# Power.net
KiCad netlist of a schematic drawn in Altium Designer
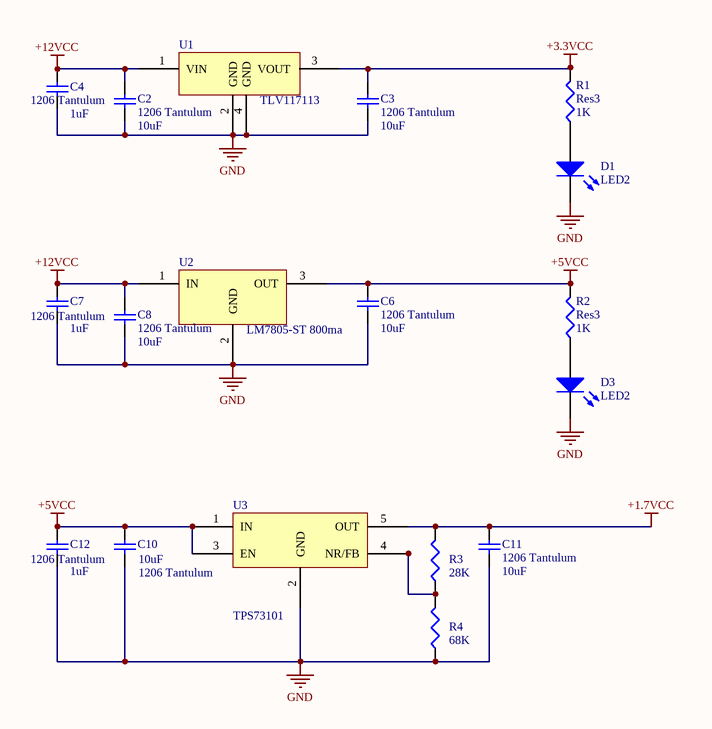
[diagram p0: Power.SchDoc]

(export (version "E")
  (design (tool "Eeschema 10.0.6"))
  (components
    (comp (ref "C2")
      (value "1206 Tantulum")
      (footprint "C1206")
      (description "Capacitor (Semiconductor SIM Model)")
      (fields (field (name "ALTIUM_VALUE") "10uF") (field (name "PUBLISHER") "Altium Limited"))
      (libsource (lib "Miscellaneous Devices") (part "Cap Semi"))
    )
    (comp (ref "C3")
      (value "1206 Tantulum")
      (footprint "C1206")
      (description "Capacitor (Semiconductor SIM Model)")
      (fields (field (name "ALTIUM_VALUE") "10uF") (field (name "PUBLISHER") "Altium Limited"))
      (libsource (lib "Miscellaneous Devices") (part "Cap Semi"))
    )
    (comp (ref "C4")
      (value "1206 Tantulum")
      (footprint "C1206")
      (description "Capacitor (Semiconductor SIM Model)")
      (fields (field (name "ALTIUM_VALUE") "1uF") (field (name "PUBLISHER") "Altium Limited"))
      (libsource (lib "Miscellaneous Devices") (part "Cap Semi"))
    )
    (comp (ref "C6")
      (value "1206 Tantulum")
      (footprint "C1206")
      (description "Capacitor (Semiconductor SIM Model)")
      (fields (field (name "ALTIUM_VALUE") "10uF") (field (name "PUBLISHER") "Altium Limited"))
      (libsource (lib "Miscellaneous Devices") (part "Cap Semi"))
    )
    (comp (ref "C7")
      (value "1206 Tantulum")
      (footprint "C1206")
      (description "Capacitor (Semiconductor SIM Model)")
      (fields (field (name "ALTIUM_VALUE") "1uF") (field (name "PUBLISHER") "Altium Limited"))
      (libsource (lib "Miscellaneous Devices") (part "Cap Semi"))
    )
    (comp (ref "C8")
      (value "1206 Tantulum")
      (footprint "C1206")
      (description "Capacitor (Semiconductor SIM Model)")
      (fields (field (name "ALTIUM_VALUE") "10uF") (field (name "PUBLISHER") "Altium Limited"))
      (libsource (lib "Miscellaneous Devices") (part "Cap Semi"))
    )
    (comp (ref "C10")
      (value "1206 Tantulum")
      (footprint "C1206")
      (description "Capacitor (Semiconductor SIM Model)")
      (fields (field (name "ALTIUM_VALUE") "10uF") (field (name "PUBLISHER") "Altium Limited"))
      (libsource (lib "Miscellaneous Devices") (part "Cap Semi"))
    )
    (comp (ref "C11")
      (value "1206 Tantulum")
      (footprint "C1206")
      (description "Capacitor (Semiconductor SIM Model)")
      (fields (field (name "ALTIUM_VALUE") "10uF") (field (name "PUBLISHER") "Altium Limited"))
      (libsource (lib "Miscellaneous Devices") (part "Cap Semi"))
    )
    (comp (ref "C12")
      (value "1206 Tantulum")
      (footprint "C1206")
      (description "Capacitor (Semiconductor SIM Model)")
      (fields (field (name "ALTIUM_VALUE") "1uF") (field (name "PUBLISHER") "Altium Limited"))
      (libsource (lib "Miscellaneous Devices") (part "Cap Semi"))
    )
    (comp (ref "D1")
      (value "LED2")
      (footprint "SM 0805 polarized")
      (description "Typical RED, GREEN, YELLOW, AMBER GaAs LED")
      (fields (field (name "PUBLISHER") "Altium Limited"))
      (libsource (lib "Miscellaneous Devices") (part "LED2"))
    )
    (comp (ref "D3")
      (value "LED2")
      (footprint "SM 0805 polarized")
      (description "Typical RED, GREEN, YELLOW, AMBER GaAs LED")
      (fields (field (name "PUBLISHER") "Altium Limited"))
      (libsource (lib "Miscellaneous Devices") (part "LED2"))
    )
    (comp (ref "R1")
      (value "Res3")
      (footprint "SM 0805 - gap trimmed")
      (description "Resistor")
      (fields (field (name "ALTIUM_VALUE") "1K") (field (name "PUBLISHER") "Altium Limited"))
      (libsource (lib "Miscellaneous Devices") (part "Res3"))
    )
    (comp (ref "R2")
      (value "Res3")
      (footprint "SM 0805 - gap trimmed")
      (description "Resistor")
      (fields (field (name "ALTIUM_VALUE") "1K") (field (name "PUBLISHER") "Altium Limited"))
      (libsource (lib "Miscellaneous Devices") (part "Res3"))
    )
    (comp (ref "R3")
      (value "28K")
      (footprint "SM 0805 - gap trimmed")
      (description "Resistor")
      (fields (field (name "Comment") "Res3") (field (name "PUBLISHER") "Altium Limited"))
      (libsource (lib "Miscellaneous Devices") (part "Res3"))
    )
    (comp (ref "R4")
      (value "68K")
      (footprint "SM 0805 - gap trimmed")
      (description "Resistor")
      (fields (field (name "Comment") "Res3") (field (name "PUBLISHER") "Altium Limited"))
      (libsource (lib "Miscellaneous Devices") (part "Res3"))
    )
    (comp (ref "U1")
      (value "TLV117113")
      (footprint "TLV117112")
      (description "Linear Regulator")
      (libsource (lib "Adams Altium Library") (part "TLV117112"))
    )
    (comp (ref "U2")
      (value "LM7805-ST 800ma")
      (footprint "DPAK-3")
      (libsource (lib "Ribbon Interface Schem Symbols") (part "LM708-ST 800ma"))
    )
    (comp (ref "U3")
      (value "TPS73101")
      (footprint "TPS73101")
      (description "Ti TPS73101 Adjustable LDO")
      (libsource (lib "Ribbon Interface Schem Symbols") (part "TPS73101"))
    )
  )
  (nets
    (net (code "1") (name "+1.7VCC") (class "Default")
      (node (ref "C11") (pin "2") (pinfunction "2_2") (pintype "passive"))
      (node (ref "R3") (pin "2") (pinfunction "2_2") (pintype "passive"))
      (node (ref "U3") (pin "5") (pinfunction "OUT_5") (pintype "passive"))
    )
    (net (code "2") (name "+3.3VCC") (class "Default")
      (node (ref "C3") (pin "2") (pinfunction "2_2") (pintype "passive"))
      (node (ref "R1") (pin "2") (pinfunction "2_2") (pintype "passive"))
      (node (ref "U1") (pin "3") (pinfunction "VOUT_3") (pintype "passive"))
    )
    (net (code "3") (name "+5VCC") (class "Default")
      (node (ref "C10") (pin "2") (pinfunction "2_2") (pintype "passive"))
      (node (ref "C12") (pin "2") (pinfunction "2_2") (pintype "passive"))
      (node (ref "C6") (pin "2") (pinfunction "2_2") (pintype "passive"))
      (node (ref "R2") (pin "2") (pinfunction "2_2") (pintype "passive"))
      (node (ref "U2") (pin "3") (pinfunction "OUT_3") (pintype "passive"))
      (node (ref "U3") (pin "1") (pinfunction "IN_1") (pintype "passive"))
      (node (ref "U3") (pin "3") (pinfunction "EN_3") (pintype "passive"))
    )
    (net (code "4") (name "+12VCC") (class "Default")
      (node (ref "C2") (pin "2") (pinfunction "2_2") (pintype "passive"))
      (node (ref "C4") (pin "2") (pinfunction "2_2") (pintype "passive"))
      (node (ref "C7") (pin "2") (pinfunction "2_2") (pintype "passive"))
      (node (ref "C8") (pin "2") (pinfunction "2_2") (pintype "passive"))
      (node (ref "U1") (pin "1") (pinfunction "VIN_1") (pintype "passive"))
      (node (ref "U2") (pin "1") (pinfunction "IN_1") (pintype "passive"))
    )
    (net (code "5") (name "GND") (class "Default")
      (node (ref "C10") (pin "1") (pinfunction "1_1") (pintype "passive"))
      (node (ref "C11") (pin "1") (pinfunction "1_1") (pintype "passive"))
      (node (ref "C12") (pin "1") (pinfunction "1_1") (pintype "passive"))
      (node (ref "C2") (pin "1") (pinfunction "1_1") (pintype "passive"))
      (node (ref "C3") (pin "1") (pinfunction "1_1") (pintype "passive"))
      (node (ref "C4") (pin "1") (pinfunction "1_1") (pintype "passive"))
      (node (ref "C6") (pin "1") (pinfunction "1_1") (pintype "passive"))
      (node (ref "C7") (pin "1") (pinfunction "1_1") (pintype "passive"))
      (node (ref "C8") (pin "1") (pinfunction "1_1") (pintype "passive"))
      (node (ref "D1") (pin "1") (pinfunction "A_1") (pintype "passive"))
      (node (ref "D3") (pin "1") (pinfunction "A_1") (pintype "passive"))
      (node (ref "R4") (pin "1") (pinfunction "1_1") (pintype "passive"))
      (node (ref "U1") (pin "2") (pinfunction "GND_2") (pintype "passive"))
      (node (ref "U1") (pin "4") (pinfunction "GND_4") (pintype "passive"))
      (node (ref "U2") (pin "2") (pinfunction "GND_2") (pintype "passive"))
      (node (ref "U3") (pin "2") (pinfunction "GND_2") (pintype "passive"))
    )
    (net (code "6") (name "Net-(D1-K)") (class "Default")
      (node (ref "D1") (pin "2") (pinfunction "K_2") (pintype "passive"))
      (node (ref "R1") (pin "1") (pinfunction "1_1") (pintype "passive"))
    )
    (net (code "7") (name "Net-(D3-K)") (class "Default")
      (node (ref "D3") (pin "2") (pinfunction "K_2") (pintype "passive"))
      (node (ref "R2") (pin "1") (pinfunction "1_1") (pintype "passive"))
    )
    (net (code "8") (name "Net-(U3-NR{slash}FB)") (class "Default")
      (node (ref "R3") (pin "1") (pinfunction "1_1") (pintype "passive"))
      (node (ref "R4") (pin "2") (pinfunction "2_2") (pintype "passive"))
      (node (ref "U3") (pin "4") (pinfunction "NR/FB_4") (pintype "passive"))
    )
  )
)
